# LED-RingCoder-v14.net
KiCad netlist of a schematic drawn in EAGLE
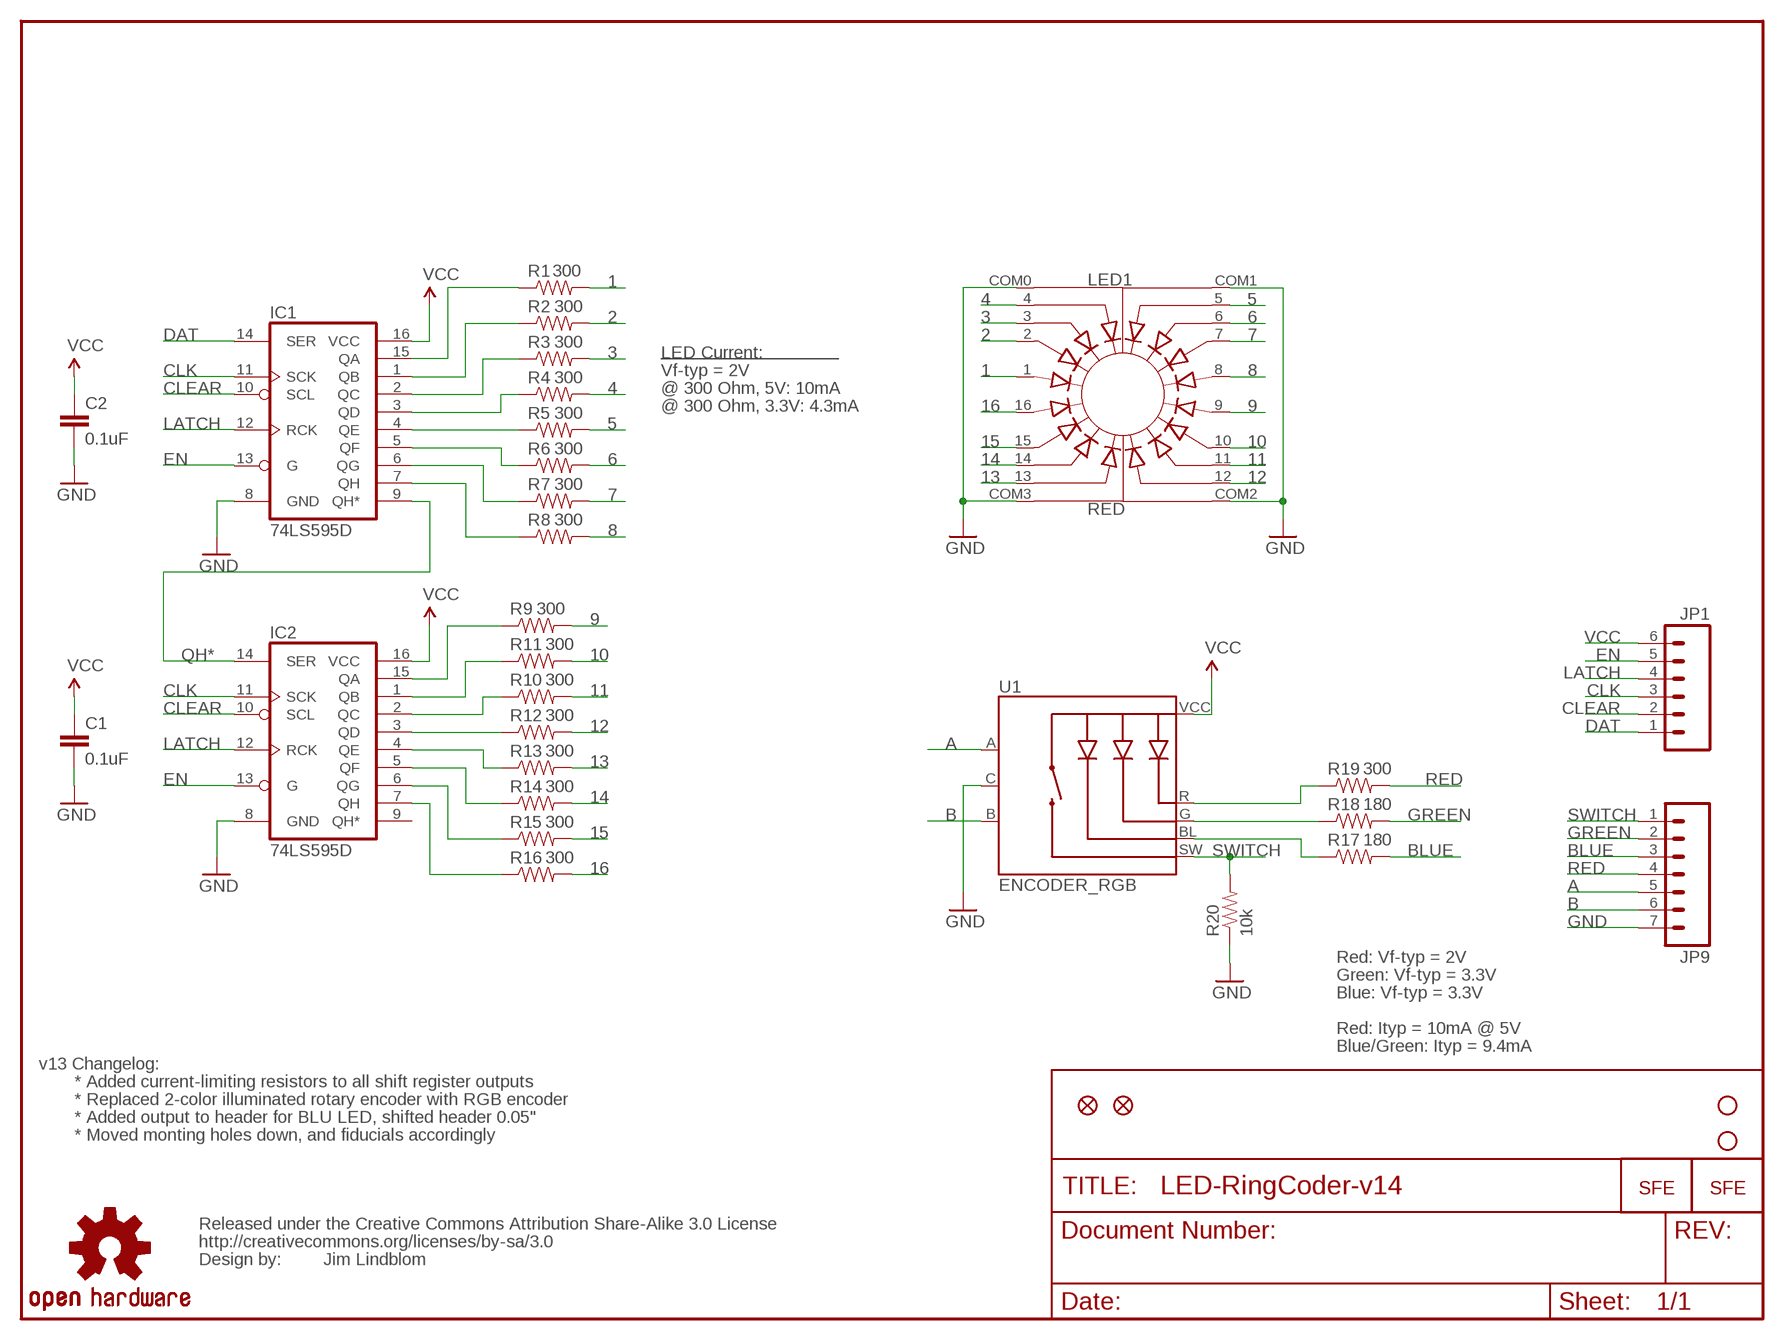
[diagram p0: schematic, sheet 1]

(export (version "E")
  (design (tool "Eeschema 10.0.6"))
  (components
    (comp (ref "C1")
      (value "0.1uF")
      (footprint "eagle-import:0402-CAP")
      (libsource (lib "eagle-import") (part "CAP0402-CAP"))
    )
    (comp (ref "C2")
      (value "0.1uF")
      (footprint "eagle-import:0402-CAP")
      (libsource (lib "eagle-import") (part "CAP0402-CAP"))
    )
    (comp (ref "IC1")
      (value "74LS595D")
      (footprint "eagle-import:SO16")
      (libsource (lib "eagle-import") (part "74595DLS"))
    )
    (comp (ref "IC2")
      (value "74LS595D")
      (footprint "eagle-import:SO16")
      (libsource (lib "eagle-import") (part "74595DLS"))
    )
    (comp (ref "JP1")
      (value "M06SIP")
      (footprint "eagle-import:1X06")
      (libsource (lib "eagle-import") (part "M06SIP"))
    )
    (comp (ref "JP2")
      (value "LOGO-SFENW2")
      (footprint "eagle-import:SFE-NEW-WEB")
      (libsource (lib "eagle-import") (part "LOGO-SFENW2"))
    )
    (comp (ref "JP3")
      (value "STAND-OFF")
      (footprint "eagle-import:STAND-OFF")
      (libsource (lib "eagle-import") (part "STAND-OFF"))
    )
    (comp (ref "JP4")
      (value "STAND-OFF")
      (footprint "eagle-import:STAND-OFF")
      (libsource (lib "eagle-import") (part "STAND-OFF"))
    )
    (comp (ref "JP5")
      (value "FIDUCIAL1X2.5")
      (footprint "eagle-import:FIDUCIAL-1X2.5")
      (libsource (lib "eagle-import") (part "FIDUCIAL1X2.5"))
    )
    (comp (ref "JP6")
      (value "LOGO-SFESK")
      (footprint "eagle-import:SFE-LOGO-FLAME")
      (libsource (lib "eagle-import") (part "LOGO-SFESK"))
    )
    (comp (ref "JP8")
      (value "FIDUCIAL1X2.5")
      (footprint "eagle-import:FIDUCIAL-1X2.5")
      (libsource (lib "eagle-import") (part "FIDUCIAL1X2.5"))
    )
    (comp (ref "JP9")
      (value "M07")
      (footprint "eagle-import:1X07")
      (libsource (lib "eagle-import") (part "M07"))
    )
    (comp (ref "LED1")
      (value "RED")
      (footprint "eagle-import:LED_RING")
      (libsource (lib "eagle-import") (part "LED_RING"))
    )
    (comp (ref "R1")
      (value "300")
      (footprint "eagle-import:0402-RES")
      (libsource (lib "eagle-import") (part "RESISTOR0402-RES"))
    )
    (comp (ref "R2")
      (value "300")
      (footprint "eagle-import:0402-RES")
      (libsource (lib "eagle-import") (part "RESISTOR0402-RES"))
    )
    (comp (ref "R3")
      (value "300")
      (footprint "eagle-import:0402-RES")
      (libsource (lib "eagle-import") (part "RESISTOR0402-RES"))
    )
    (comp (ref "R4")
      (value "300")
      (footprint "eagle-import:0402-RES")
      (libsource (lib "eagle-import") (part "RESISTOR0402-RES"))
    )
    (comp (ref "R5")
      (value "300")
      (footprint "eagle-import:0402-RES")
      (libsource (lib "eagle-import") (part "RESISTOR0402-RES"))
    )
    (comp (ref "R6")
      (value "300")
      (footprint "eagle-import:0402-RES")
      (libsource (lib "eagle-import") (part "RESISTOR0402-RES"))
    )
    (comp (ref "R7")
      (value "300")
      (footprint "eagle-import:0402-RES")
      (libsource (lib "eagle-import") (part "RESISTOR0402-RES"))
    )
    (comp (ref "R8")
      (value "300")
      (footprint "eagle-import:0402-RES")
      (libsource (lib "eagle-import") (part "RESISTOR0402-RES"))
    )
    (comp (ref "R9")
      (value "300")
      (footprint "eagle-import:0402-RES")
      (libsource (lib "eagle-import") (part "RESISTOR0402-RES"))
    )
    (comp (ref "R10")
      (value "300")
      (footprint "eagle-import:0402-RES")
      (libsource (lib "eagle-import") (part "RESISTOR0402-RES"))
    )
    (comp (ref "R11")
      (value "300")
      (footprint "eagle-import:0402-RES")
      (libsource (lib "eagle-import") (part "RESISTOR0402-RES"))
    )
    (comp (ref "R12")
      (value "300")
      (footprint "eagle-import:0402-RES")
      (libsource (lib "eagle-import") (part "RESISTOR0402-RES"))
    )
    (comp (ref "R13")
      (value "300")
      (footprint "eagle-import:0402-RES")
      (libsource (lib "eagle-import") (part "RESISTOR0402-RES"))
    )
    (comp (ref "R14")
      (value "300")
      (footprint "eagle-import:0402-RES")
      (libsource (lib "eagle-import") (part "RESISTOR0402-RES"))
    )
    (comp (ref "R15")
      (value "300")
      (footprint "eagle-import:0402-RES")
      (libsource (lib "eagle-import") (part "RESISTOR0402-RES"))
    )
    (comp (ref "R16")
      (value "300")
      (footprint "eagle-import:0402-RES")
      (libsource (lib "eagle-import") (part "RESISTOR0402-RES"))
    )
    (comp (ref "R17")
      (value "180")
      (footprint "eagle-import:0402-RES")
      (libsource (lib "eagle-import") (part "RESISTOR0402-RES"))
    )
    (comp (ref "R18")
      (value "180")
      (footprint "eagle-import:0402-RES")
      (libsource (lib "eagle-import") (part "RESISTOR0402-RES"))
    )
    (comp (ref "R19")
      (value "300")
      (footprint "eagle-import:0402-RES")
      (libsource (lib "eagle-import") (part "RESISTOR0402-RES"))
    )
    (comp (ref "R20")
      (value "10k")
      (footprint "eagle-import:0402-RES")
      (libsource (lib "eagle-import") (part "RESISTOR0402-RES"))
    )
    (comp (ref "U$1")
      (value "CREATIVE_COMMONS")
      (footprint "eagle-import:CREATIVE_COMMONS")
      (libsource (lib "eagle-import") (part "CREATIVE_COMMONS"))
    )
    (comp (ref "U$2")
      (value "OSHW-LOGOS")
      (footprint "eagle-import:OSHW-LOGO-S")
      (libsource (lib "eagle-import") (part "OSHW-LOGOS"))
    )
    (comp (ref "U1")
      (value "ENCODER_RGB")
      (footprint "eagle-import:ENCODER_LED_RGB")
      (libsource (lib "eagle-import") (part "ENCODER_RGB"))
    )
  )
  (nets
    (net (code "1") (name "/1") (class "Default")
      (node (ref "LED1") (pin "1") (pinfunction "1_1") (pintype "passive"))
      (node (ref "R1") (pin "2") (pinfunction "2_2") (pintype "passive"))
    )
    (net (code "2") (name "/2") (class "Default")
      (node (ref "LED1") (pin "2") (pinfunction "2_2") (pintype "passive"))
      (node (ref "R2") (pin "2") (pinfunction "2_2") (pintype "passive"))
    )
    (net (code "3") (name "/3") (class "Default")
      (node (ref "LED1") (pin "3") (pinfunction "3_3") (pintype "passive"))
      (node (ref "R3") (pin "2") (pinfunction "2_2") (pintype "passive"))
    )
    (net (code "4") (name "/4") (class "Default")
      (node (ref "LED1") (pin "4") (pinfunction "4_4") (pintype "passive"))
      (node (ref "R4") (pin "2") (pinfunction "2_2") (pintype "passive"))
    )
    (net (code "5") (name "/5") (class "Default")
      (node (ref "LED1") (pin "5") (pinfunction "5_5") (pintype "passive"))
      (node (ref "R5") (pin "2") (pinfunction "2_2") (pintype "passive"))
    )
    (net (code "6") (name "/6") (class "Default")
      (node (ref "LED1") (pin "6") (pinfunction "6_6") (pintype "passive"))
      (node (ref "R6") (pin "2") (pinfunction "2_2") (pintype "passive"))
    )
    (net (code "7") (name "/7") (class "Default")
      (node (ref "LED1") (pin "7") (pinfunction "7_7") (pintype "passive"))
      (node (ref "R7") (pin "2") (pinfunction "2_2") (pintype "passive"))
    )
    (net (code "8") (name "/8") (class "Default")
      (node (ref "LED1") (pin "8") (pinfunction "8_8") (pintype "passive"))
      (node (ref "R8") (pin "2") (pinfunction "2_2") (pintype "passive"))
    )
    (net (code "9") (name "/9") (class "Default")
      (node (ref "LED1") (pin "9") (pinfunction "9_9") (pintype "passive"))
      (node (ref "R9") (pin "2") (pinfunction "2_2") (pintype "passive"))
    )
    (net (code "10") (name "/10") (class "Default")
      (node (ref "LED1") (pin "10") (pinfunction "10_10") (pintype "passive"))
      (node (ref "R11") (pin "2") (pinfunction "2_2") (pintype "passive"))
    )
    (net (code "11") (name "/11") (class "Default")
      (node (ref "LED1") (pin "11") (pinfunction "11_11") (pintype "passive"))
      (node (ref "R10") (pin "2") (pinfunction "2_2") (pintype "passive"))
    )
    (net (code "12") (name "/12") (class "Default")
      (node (ref "LED1") (pin "12") (pinfunction "12_12") (pintype "passive"))
      (node (ref "R12") (pin "2") (pinfunction "2_2") (pintype "passive"))
    )
    (net (code "13") (name "/13") (class "Default")
      (node (ref "LED1") (pin "13") (pinfunction "13_13") (pintype "passive"))
      (node (ref "R13") (pin "2") (pinfunction "2_2") (pintype "passive"))
    )
    (net (code "14") (name "/14") (class "Default")
      (node (ref "LED1") (pin "14") (pinfunction "14_14") (pintype "passive"))
      (node (ref "R14") (pin "2") (pinfunction "2_2") (pintype "passive"))
    )
    (net (code "15") (name "/15") (class "Default")
      (node (ref "LED1") (pin "15") (pinfunction "15_15") (pintype "passive"))
      (node (ref "R15") (pin "2") (pinfunction "2_2") (pintype "passive"))
    )
    (net (code "16") (name "/16") (class "Default")
      (node (ref "LED1") (pin "16") (pinfunction "16_16") (pintype "passive"))
      (node (ref "R16") (pin "2") (pinfunction "2_2") (pintype "passive"))
    )
    (net (code "17") (name "/A") (class "Default")
      (node (ref "JP9") (pin "5") (pinfunction "5_5") (pintype "passive"))
      (node (ref "U1") (pin "A") (pinfunction "A_A") (pintype "bidirectional"))
    )
    (net (code "18") (name "/B") (class "Default")
      (node (ref "JP9") (pin "6") (pinfunction "6_6") (pintype "passive"))
      (node (ref "U1") (pin "B") (pinfunction "B_B") (pintype "bidirectional"))
    )
    (net (code "19") (name "/BLUE") (class "Default")
      (node (ref "JP9") (pin "3") (pinfunction "3_3") (pintype "passive"))
      (node (ref "R17") (pin "2") (pinfunction "2_2") (pintype "passive"))
    )
    (net (code "20") (name "/CLEAR") (class "Default")
      (node (ref "IC1") (pin "10") (pinfunction "SCL_10") (pintype "input"))
      (node (ref "IC2") (pin "10") (pinfunction "SCL_10") (pintype "input"))
      (node (ref "JP1") (pin "2") (pinfunction "2_2") (pintype "passive"))
    )
    (net (code "21") (name "/CLK") (class "Default")
      (node (ref "IC1") (pin "11") (pinfunction "SCK_11") (pintype "input"))
      (node (ref "IC2") (pin "11") (pinfunction "SCK_11") (pintype "input"))
      (node (ref "JP1") (pin "3") (pinfunction "3_3") (pintype "passive"))
    )
    (net (code "22") (name "/DAT") (class "Default")
      (node (ref "IC1") (pin "14") (pinfunction "SER_14") (pintype "input"))
      (node (ref "JP1") (pin "1") (pinfunction "1_1") (pintype "passive"))
    )
    (net (code "23") (name "/EN") (class "Default")
      (node (ref "IC1") (pin "13") (pinfunction "G_13") (pintype "input"))
      (node (ref "IC2") (pin "13") (pinfunction "G_13") (pintype "input"))
      (node (ref "JP1") (pin "5") (pinfunction "5_5") (pintype "passive"))
    )
    (net (code "24") (name "/GREEN") (class "Default")
      (node (ref "JP9") (pin "2") (pinfunction "2_2") (pintype "passive"))
      (node (ref "R18") (pin "2") (pinfunction "2_2") (pintype "passive"))
    )
    (net (code "25") (name "/LATCH") (class "Default")
      (node (ref "IC1") (pin "12") (pinfunction "RCK_12") (pintype "input"))
      (node (ref "IC2") (pin "12") (pinfunction "RCK_12") (pintype "input"))
      (node (ref "JP1") (pin "4") (pinfunction "4_4") (pintype "passive"))
    )
    (net (code "26") (name "/QH*") (class "Default")
      (node (ref "IC1") (pin "9") (pinfunction "QH*_9") (pintype "tri_state"))
      (node (ref "IC2") (pin "14") (pinfunction "SER_14") (pintype "input"))
    )
    (net (code "27") (name "/RED") (class "Default")
      (node (ref "JP9") (pin "4") (pinfunction "4_4") (pintype "passive"))
      (node (ref "R19") (pin "2") (pinfunction "2_2") (pintype "passive"))
    )
    (net (code "28") (name "/SWITCH") (class "Default")
      (node (ref "JP9") (pin "1") (pinfunction "1_1") (pintype "passive"))
      (node (ref "R20") (pin "2") (pinfunction "2_2") (pintype "passive"))
      (node (ref "U1") (pin "SW") (pinfunction "SW_SW") (pintype "passive"))
    )
    (net (code "29") (name "GND") (class "Default")
      (node (ref "C1") (pin "2") (pinfunction "2_2") (pintype "passive"))
      (node (ref "C2") (pin "2") (pinfunction "2_2") (pintype "passive"))
      (node (ref "IC1") (pin "8") (pinfunction "GND_8") (pintype "power_in"))
      (node (ref "IC2") (pin "8") (pinfunction "GND_8") (pintype "power_in"))
      (node (ref "JP9") (pin "7") (pinfunction "7_7") (pintype "passive"))
      (node (ref "LED1") (pin "COM0") (pinfunction "COM0_COM0") (pintype "passive"))
      (node (ref "LED1") (pin "COM1") (pinfunction "COM1_COM1") (pintype "passive"))
      (node (ref "LED1") (pin "COM2") (pinfunction "COM2_COM2") (pintype "passive"))
      (node (ref "LED1") (pin "COM3") (pinfunction "COM3_COM3") (pintype "passive"))
      (node (ref "R20") (pin "1") (pinfunction "1_1") (pintype "passive"))
      (node (ref "U1") (pin "C") (pinfunction "C_C") (pintype "bidirectional"))
    )
    (net (code "30") (name "Net-(IC1-QA)") (class "Default")
      (node (ref "IC1") (pin "15") (pinfunction "QA_15") (pintype "tri_state"))
      (node (ref "R1") (pin "1") (pinfunction "1_1") (pintype "passive"))
    )
    (net (code "31") (name "Net-(IC1-QB)") (class "Default")
      (node (ref "IC1") (pin "1") (pinfunction "QB_1") (pintype "tri_state"))
      (node (ref "R2") (pin "1") (pinfunction "1_1") (pintype "passive"))
    )
    (net (code "32") (name "Net-(IC1-QC)") (class "Default")
      (node (ref "IC1") (pin "2") (pinfunction "QC_2") (pintype "tri_state"))
      (node (ref "R3") (pin "1") (pinfunction "1_1") (pintype "passive"))
    )
    (net (code "33") (name "Net-(IC1-QD)") (class "Default")
      (node (ref "IC1") (pin "3") (pinfunction "QD_3") (pintype "tri_state"))
      (node (ref "R4") (pin "1") (pinfunction "1_1") (pintype "passive"))
    )
    (net (code "34") (name "Net-(IC1-QE)") (class "Default")
      (node (ref "IC1") (pin "4") (pinfunction "QE_4") (pintype "tri_state"))
      (node (ref "R5") (pin "1") (pinfunction "1_1") (pintype "passive"))
    )
    (net (code "35") (name "Net-(IC1-QF)") (class "Default")
      (node (ref "IC1") (pin "5") (pinfunction "QF_5") (pintype "tri_state"))
      (node (ref "R6") (pin "1") (pinfunction "1_1") (pintype "passive"))
    )
    (net (code "36") (name "Net-(IC1-QG)") (class "Default")
      (node (ref "IC1") (pin "6") (pinfunction "QG_6") (pintype "tri_state"))
      (node (ref "R7") (pin "1") (pinfunction "1_1") (pintype "passive"))
    )
    (net (code "37") (name "Net-(IC1-QH)") (class "Default")
      (node (ref "IC1") (pin "7") (pinfunction "QH_7") (pintype "tri_state"))
      (node (ref "R8") (pin "1") (pinfunction "1_1") (pintype "passive"))
    )
    (net (code "38") (name "Net-(IC2-QA)") (class "Default")
      (node (ref "IC2") (pin "15") (pinfunction "QA_15") (pintype "tri_state"))
      (node (ref "R9") (pin "1") (pinfunction "1_1") (pintype "passive"))
    )
    (net (code "39") (name "Net-(IC2-QB)") (class "Default")
      (node (ref "IC2") (pin "1") (pinfunction "QB_1") (pintype "tri_state"))
      (node (ref "R11") (pin "1") (pinfunction "1_1") (pintype "passive"))
    )
    (net (code "40") (name "Net-(IC2-QC)") (class "Default")
      (node (ref "IC2") (pin "2") (pinfunction "QC_2") (pintype "tri_state"))
      (node (ref "R10") (pin "1") (pinfunction "1_1") (pintype "passive"))
    )
    (net (code "41") (name "Net-(IC2-QD)") (class "Default")
      (node (ref "IC2") (pin "3") (pinfunction "QD_3") (pintype "tri_state"))
      (node (ref "R12") (pin "1") (pinfunction "1_1") (pintype "passive"))
    )
    (net (code "42") (name "Net-(IC2-QE)") (class "Default")
      (node (ref "IC2") (pin "4") (pinfunction "QE_4") (pintype "tri_state"))
      (node (ref "R13") (pin "1") (pinfunction "1_1") (pintype "passive"))
    )
    (net (code "43") (name "Net-(IC2-QF)") (class "Default")
      (node (ref "IC2") (pin "5") (pinfunction "QF_5") (pintype "tri_state"))
      (node (ref "R14") (pin "1") (pinfunction "1_1") (pintype "passive"))
    )
    (net (code "44") (name "Net-(IC2-QG)") (class "Default")
      (node (ref "IC2") (pin "6") (pinfunction "QG_6") (pintype "tri_state"))
      (node (ref "R15") (pin "1") (pinfunction "1_1") (pintype "passive"))
    )
    (net (code "45") (name "Net-(IC2-QH)") (class "Default")
      (node (ref "IC2") (pin "7") (pinfunction "QH_7") (pintype "tri_state"))
      (node (ref "R16") (pin "1") (pinfunction "1_1") (pintype "passive"))
    )
    (net (code "46") (name "Net-(R17-Pad1)") (class "Default")
      (node (ref "R17") (pin "1") (pinfunction "1_1") (pintype "passive"))
      (node (ref "U1") (pin "BL") (pinfunction "BL_BL") (pintype "passive"))
    )
    (net (code "47") (name "Net-(R18-Pad1)") (class "Default")
      (node (ref "R18") (pin "1") (pinfunction "1_1") (pintype "passive"))
      (node (ref "U1") (pin "G") (pinfunction "G_G") (pintype "passive"))
    )
    (net (code "48") (name "Net-(R19-Pad1)") (class "Default")
      (node (ref "R19") (pin "1") (pinfunction "1_1") (pintype "passive"))
      (node (ref "U1") (pin "R") (pinfunction "R_R") (pintype "passive"))
    )
    (net (code "49") (name "VCC") (class "Default")
      (node (ref "C1") (pin "1") (pinfunction "1_1") (pintype "passive"))
      (node (ref "C2") (pin "1") (pinfunction "1_1") (pintype "passive"))
      (node (ref "IC1") (pin "16") (pinfunction "VCC_16") (pintype "power_in"))
      (node (ref "IC2") (pin "16") (pinfunction "VCC_16") (pintype "power_in"))
      (node (ref "JP1") (pin "6") (pinfunction "6_6") (pintype "passive"))
      (node (ref "U1") (pin "VCC") (pinfunction "VCC_VCC") (pintype "passive"))
    )
    (net (code "50") (name "unconnected-(IC2-QH*-Pad9)") (class "Default")
      (node (ref "IC2") (pin "9") (pinfunction "QH*_9") (pintype "tri_state"))
    )
  )
)
